# MCU_v3.net
KiCad netlist of a schematic drawn in EAGLE
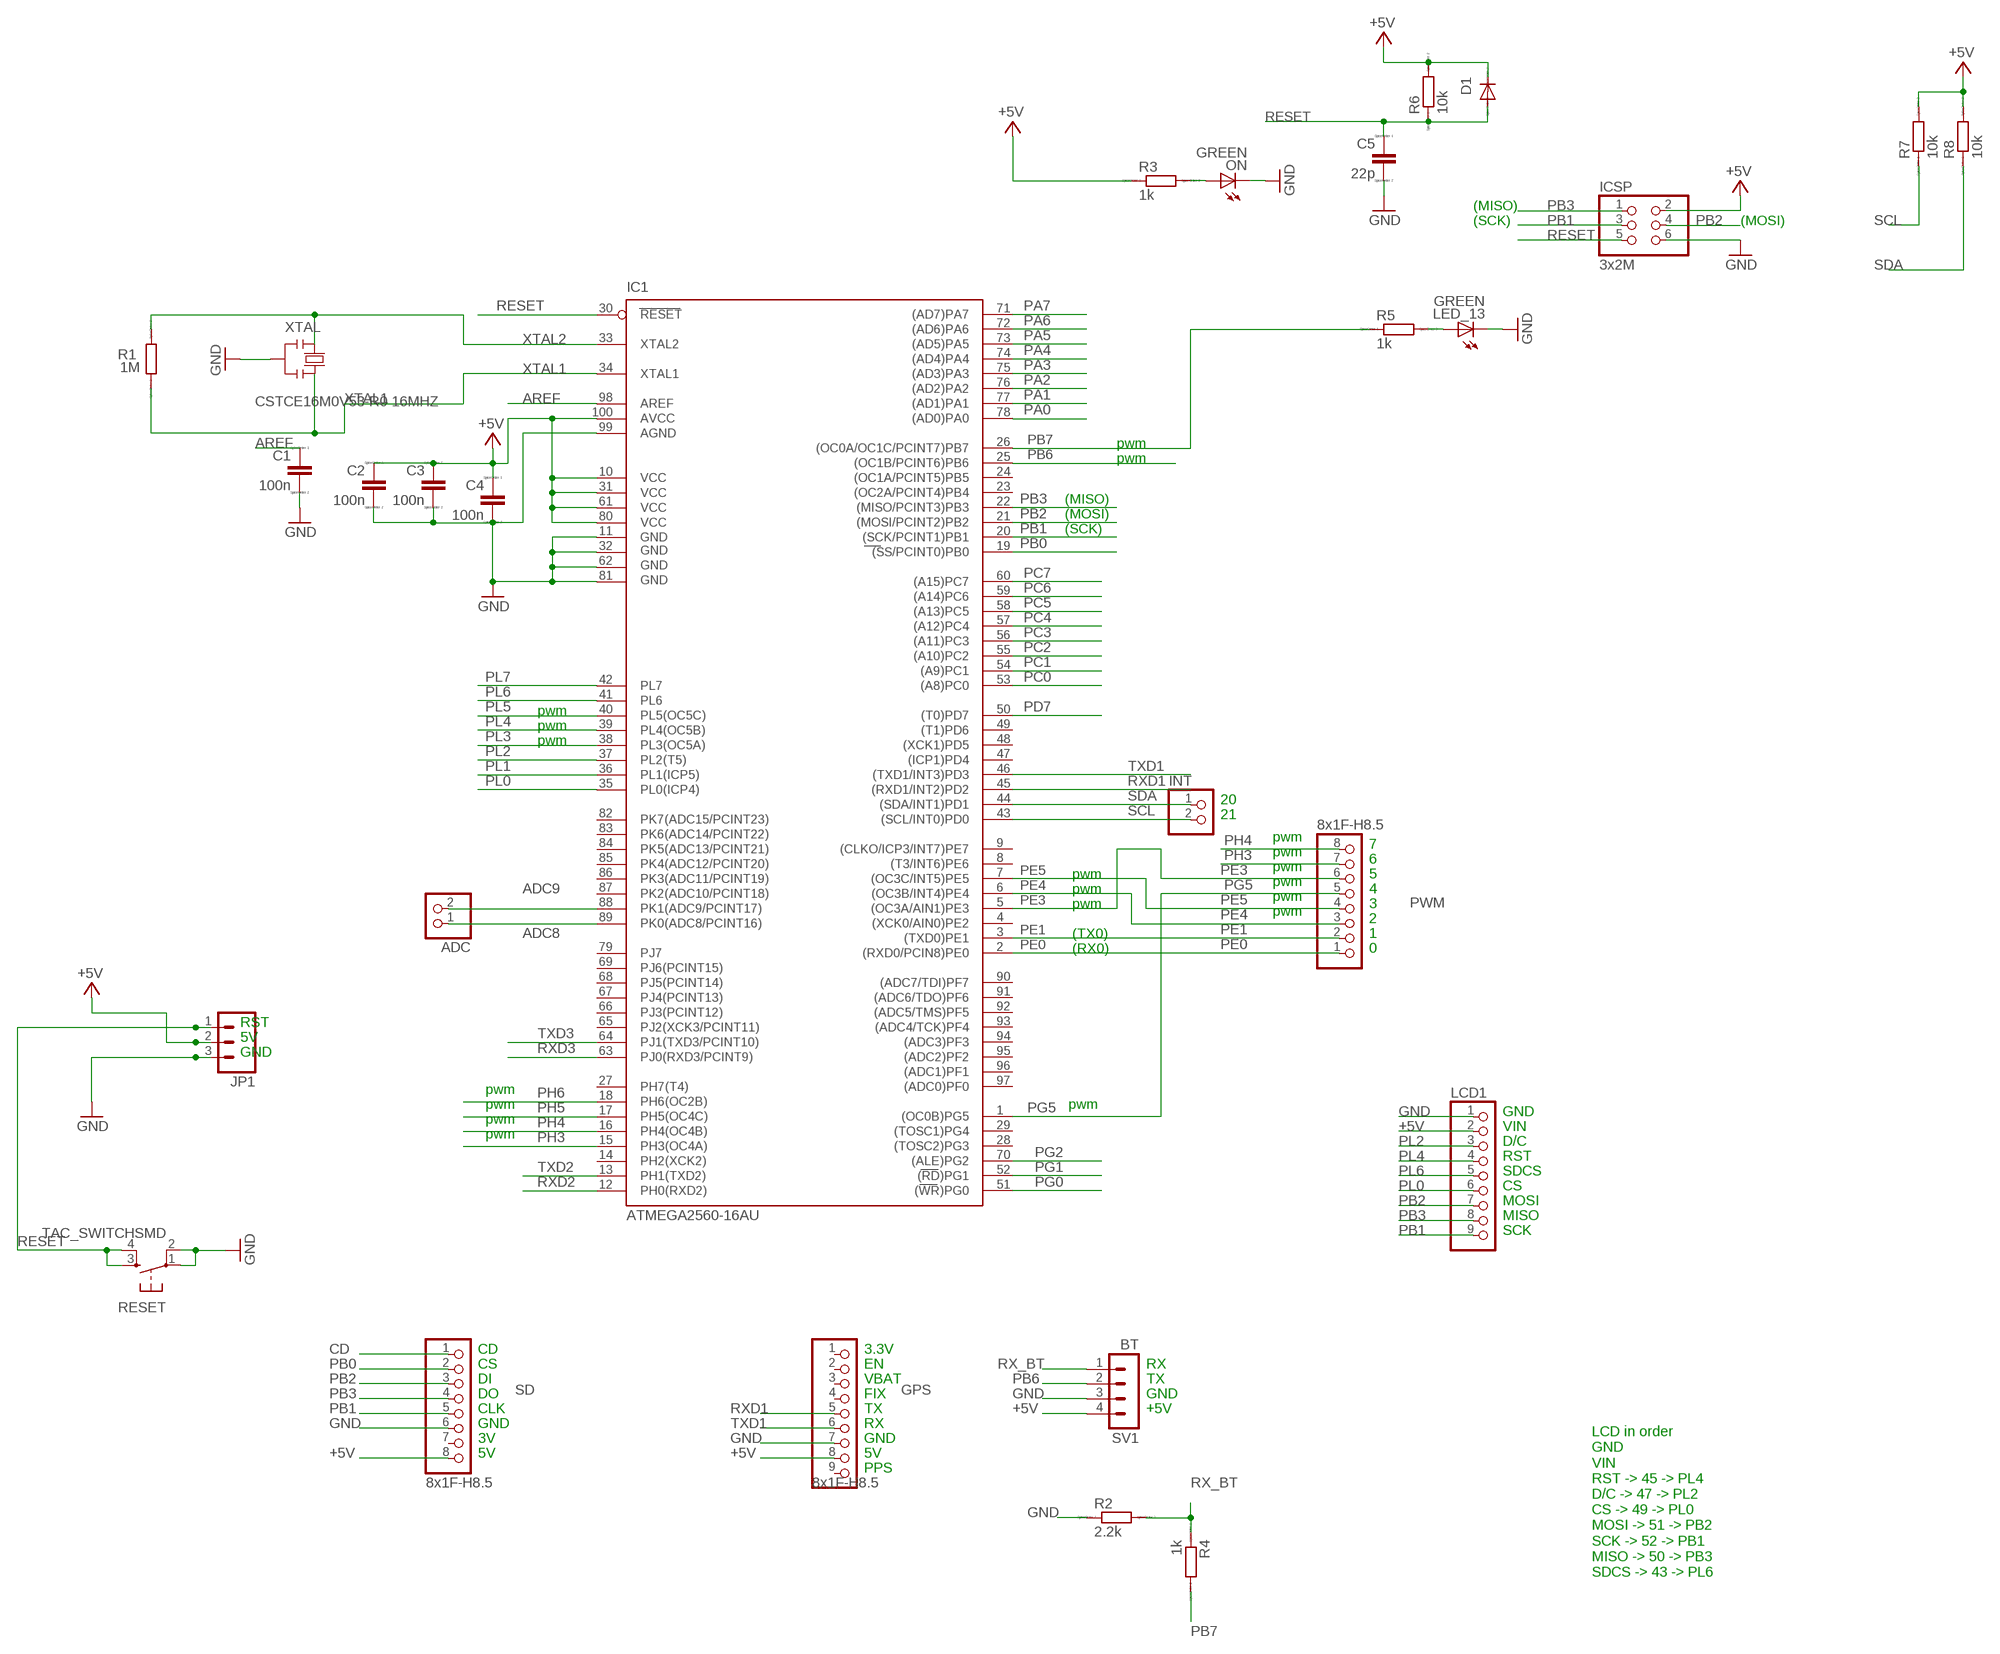
[diagram p0: schematic, sheet 1]

(export (version "E")
  (design (tool "Eeschema 10.0.6"))
  (components
    (comp (ref "ADC")
      (value "PINHD-1X2")
      (footprint "eagle-import:1X02")
      (fields (field (name "MPN") "A21-X0-22-507-115-E"))
      (libsource (lib "eagle-import") (part "PINHD-1X2"))
    )
    (comp (ref "C1")
      (value "100n")
      (footprint "eagle-import:C0805")
      (libsource (lib "eagle-import") (part "C-EUC0805"))
    )
    (comp (ref "C2")
      (value "100n")
      (footprint "eagle-import:C0805")
      (libsource (lib "eagle-import") (part "C-EUC0805"))
    )
    (comp (ref "C3")
      (value "100n")
      (footprint "eagle-import:C0805")
      (libsource (lib "eagle-import") (part "C-EUC0805"))
    )
    (comp (ref "C4")
      (value "100n")
      (footprint "eagle-import:C0805")
      (libsource (lib "eagle-import") (part "C-EUC0805"))
    )
    (comp (ref "C5")
      (value "22p")
      (footprint "eagle-import:C0805")
      (libsource (lib "eagle-import") (part "C-EUC0805"))
    )
    (comp (ref "D1")
      (value "DIODE-MINIMELF")
      (footprint "eagle-import:MINIMELF")
      (libsource (lib "eagle-import") (part "DIODE-MINIMELF"))
    )
    (comp (ref "GPS")
      (value "8x1F-H8.5")
      (footprint "eagle-import:1X09")
      (libsource (lib "eagle-import") (part "PINHD-1X9"))
    )
    (comp (ref "IC1")
      (value "ATMEGA2560-16AU")
      (footprint "eagle-import:TQFP100")
      (libsource (lib "eagle-import") (part "ATMEGA2560AU2560-16"))
    )
    (comp (ref "ICSP")
      (value "3x2M")
      (footprint "eagle-import:2X03")
      (libsource (lib "eagle-import") (part "PINHD-2X3"))
    )
    (comp (ref "INT")
      (value "PINHD-1X2")
      (footprint "eagle-import:1X02")
      (fields (field (name "MPN") "A21-X0-22-507-115-E"))
      (libsource (lib "eagle-import") (part "PINHD-1X2"))
    )
    (comp (ref "JP1")
      (value "M03PTH")
      (footprint "eagle-import:1X03")
      (fields (field (name "MPN") "BI2-Q10S-AZ31X-0.3M-SB3T"))
      (libsource (lib "eagle-import") (part "M03PTH"))
    )
    (comp (ref "LCD1")
      (value "PINHD-1X9")
      (footprint "eagle-import:1X09")
      (libsource (lib "eagle-import") (part "PINHD-1X9"))
    )
    (comp (ref "LED_13")
      (value "GREEN")
      (footprint "eagle-import:CHIP-LED0805")
      (libsource (lib "eagle-import") (part "LEDCHIP-LED0805"))
    )
    (comp (ref "ON")
      (value "GREEN")
      (footprint "eagle-import:CHIP-LED0805")
      (libsource (lib "eagle-import") (part "LEDCHIP-LED0805"))
    )
    (comp (ref "PWM")
      (value "8x1F-H8.5")
      (footprint "eagle-import:1X08")
      (libsource (lib "eagle-import") (part "PINHD-1X8"))
    )
    (comp (ref "R1")
      (value "1M")
      (footprint "eagle-import:R0805")
      (libsource (lib "eagle-import") (part "R-EU_R0805"))
    )
    (comp (ref "R2")
      (value "2.2k")
      (footprint "eagle-import:R0805")
      (libsource (lib "eagle-import") (part "R-EU_R0805"))
    )
    (comp (ref "R3")
      (value "1k")
      (footprint "eagle-import:R0805")
      (libsource (lib "eagle-import") (part "R-EU_R0805"))
    )
    (comp (ref "R4")
      (value "1k")
      (footprint "eagle-import:R0805")
      (libsource (lib "eagle-import") (part "R-EU_R0805"))
    )
    (comp (ref "R5")
      (value "1k")
      (footprint "eagle-import:R0805")
      (libsource (lib "eagle-import") (part "R-EU_R0805"))
    )
    (comp (ref "R6")
      (value "10k")
      (footprint "eagle-import:R0805")
      (libsource (lib "eagle-import") (part "R-EU_R0805"))
    )
    (comp (ref "R7")
      (value "10k")
      (footprint "eagle-import:R0805")
      (libsource (lib "eagle-import") (part "R-EU_R0805"))
    )
    (comp (ref "R8")
      (value "10k")
      (footprint "eagle-import:R0805")
      (libsource (lib "eagle-import") (part "R-EU_R0805"))
    )
    (comp (ref "RESET")
      (value "TAC_SWITCHSMD")
      (footprint "eagle-import:TACTILE-SWITCH-SMD")
      (libsource (lib "eagle-import") (part "TAC_SWITCHSMD"))
    )
    (comp (ref "SD")
      (value "8x1F-H8.5")
      (footprint "eagle-import:1X08")
      (libsource (lib "eagle-import") (part "PINHD-1X8"))
    )
    (comp (ref "SV1")
      (value "BT")
      (footprint "eagle-import:MA04-1")
      (libsource (lib "eagle-import") (part "MA04-1"))
    )
    (comp (ref "XTAL")
      (value "CSTCE16M0V53-R0 16MHZ")
      (footprint "eagle-import:RESONATOR")
      (libsource (lib "eagle-import") (part "RESONATORMU"))
    )
  )
  (nets
    (net (code "1") (name "+5V") (class "Default")
      (node (ref "C2") (pin "1") (pinfunction "1_1") (pintype "passive"))
      (node (ref "C3") (pin "1") (pinfunction "1_1") (pintype "passive"))
      (node (ref "C4") (pin "1") (pinfunction "1_1") (pintype "passive"))
      (node (ref "D1") (pin "C") (pinfunction "C_C") (pintype "passive"))
      (node (ref "GPS") (pin "8") (pinfunction "8_8") (pintype "passive"))
      (node (ref "IC1") (pin "10") (pinfunction "VCC_10") (pintype "power_in"))
      (node (ref "IC1") (pin "100") (pinfunction "AVCC_100") (pintype "power_in"))
      (node (ref "IC1") (pin "31") (pinfunction "VCC1_31") (pintype "power_in"))
      (node (ref "IC1") (pin "61") (pinfunction "VCC2_61") (pintype "power_in"))
      (node (ref "IC1") (pin "80") (pinfunction "VCC3_80") (pintype "power_in"))
      (node (ref "ICSP") (pin "2") (pinfunction "2_2") (pintype "passive"))
      (node (ref "JP1") (pin "2") (pinfunction "2_2") (pintype "passive"))
      (node (ref "LCD1") (pin "2") (pinfunction "2_2") (pintype "passive"))
      (node (ref "R3") (pin "1") (pinfunction "1_1") (pintype "passive"))
      (node (ref "R6") (pin "2") (pinfunction "2_2") (pintype "passive"))
      (node (ref "R7") (pin "2") (pinfunction "2_2") (pintype "passive"))
      (node (ref "R8") (pin "2") (pinfunction "2_2") (pintype "passive"))
      (node (ref "SD") (pin "8") (pinfunction "8_8") (pintype "passive"))
      (node (ref "SV1") (pin "4") (pinfunction "4_4") (pintype "passive"))
    )
    (net (code "2") (name "/ADC8") (class "Default")
      (node (ref "ADC") (pin "1") (pinfunction "1_1") (pintype "passive"))
      (node (ref "IC1") (pin "89") (pinfunction "PK0(ADC8/PCINT16)_89") (pintype "bidirectional"))
    )
    (net (code "3") (name "/ADC9") (class "Default")
      (node (ref "ADC") (pin "2") (pinfunction "2_2") (pintype "passive"))
      (node (ref "IC1") (pin "88") (pinfunction "PK1(ADC9/PCINT17)_88") (pintype "bidirectional"))
    )
    (net (code "4") (name "/AREF") (class "Default")
      (node (ref "C1") (pin "1") (pinfunction "1_1") (pintype "passive"))
      (node (ref "IC1") (pin "98") (pinfunction "AREF_98") (pintype "bidirectional"))
    )
    (net (code "5") (name "/CD") (class "Default")
      (node (ref "SD") (pin "1") (pinfunction "1_1") (pintype "passive"))
    )
    (net (code "6") (name "/PA0") (class "Default")
      (node (ref "IC1") (pin "78") (pinfunction "(AD0)PA0_78") (pintype "bidirectional"))
    )
    (net (code "7") (name "/PA1") (class "Default")
      (node (ref "IC1") (pin "77") (pinfunction "(AD1)PA1_77") (pintype "bidirectional"))
    )
    (net (code "8") (name "/PA2") (class "Default")
      (node (ref "IC1") (pin "76") (pinfunction "(AD2)PA2_76") (pintype "bidirectional"))
    )
    (net (code "9") (name "/PA3") (class "Default")
      (node (ref "IC1") (pin "75") (pinfunction "(AD3)PA3_75") (pintype "bidirectional"))
    )
    (net (code "10") (name "/PA4") (class "Default")
      (node (ref "IC1") (pin "74") (pinfunction "(AD4)PA4_74") (pintype "bidirectional"))
    )
    (net (code "11") (name "/PA5") (class "Default")
      (node (ref "IC1") (pin "73") (pinfunction "(AD5)PA5_73") (pintype "bidirectional"))
    )
    (net (code "12") (name "/PA6") (class "Default")
      (node (ref "IC1") (pin "72") (pinfunction "(AD6)PA6_72") (pintype "bidirectional"))
    )
    (net (code "13") (name "/PA7") (class "Default")
      (node (ref "IC1") (pin "71") (pinfunction "(AD7)PA7_71") (pintype "bidirectional"))
    )
    (net (code "14") (name "/PB0") (class "Default")
      (node (ref "IC1") (pin "19") (pinfunction "(SS/PCINT0)PB0_19") (pintype "bidirectional"))
      (node (ref "SD") (pin "2") (pinfunction "2_2") (pintype "passive"))
    )
    (net (code "15") (name "/PB1") (class "Default")
      (node (ref "IC1") (pin "20") (pinfunction "(SCK/PCINT1)PB1_20") (pintype "bidirectional"))
      (node (ref "ICSP") (pin "3") (pinfunction "3_3") (pintype "passive"))
      (node (ref "LCD1") (pin "9") (pinfunction "9_9") (pintype "passive"))
      (node (ref "SD") (pin "5") (pinfunction "5_5") (pintype "passive"))
    )
    (net (code "16") (name "/PB2") (class "Default")
      (node (ref "IC1") (pin "21") (pinfunction "(MOSI/PCINT2)PB2_21") (pintype "bidirectional"))
      (node (ref "ICSP") (pin "4") (pinfunction "4_4") (pintype "passive"))
      (node (ref "LCD1") (pin "7") (pinfunction "7_7") (pintype "passive"))
      (node (ref "SD") (pin "3") (pinfunction "3_3") (pintype "passive"))
    )
    (net (code "17") (name "/PB3") (class "Default")
      (node (ref "IC1") (pin "22") (pinfunction "(MISO/PCINT3)PB3_22") (pintype "bidirectional"))
      (node (ref "ICSP") (pin "1") (pinfunction "1_1") (pintype "passive"))
      (node (ref "LCD1") (pin "8") (pinfunction "8_8") (pintype "passive"))
      (node (ref "SD") (pin "4") (pinfunction "4_4") (pintype "passive"))
    )
    (net (code "18") (name "/PB6") (class "Default")
      (node (ref "IC1") (pin "25") (pinfunction "(OC1B/PCINT6)PB6_25") (pintype "bidirectional"))
      (node (ref "SV1") (pin "2") (pinfunction "2_2") (pintype "passive"))
    )
    (net (code "19") (name "/PB7") (class "Default")
      (node (ref "IC1") (pin "26") (pinfunction "(OC0A/OC1C/PCINT7)PB7_26") (pintype "bidirectional"))
      (node (ref "R4") (pin "2") (pinfunction "2_2") (pintype "passive"))
      (node (ref "R5") (pin "1") (pinfunction "1_1") (pintype "passive"))
    )
    (net (code "20") (name "/PC0") (class "Default")
      (node (ref "IC1") (pin "53") (pinfunction "(A8)PC0_53") (pintype "bidirectional"))
    )
    (net (code "21") (name "/PC1") (class "Default")
      (node (ref "IC1") (pin "54") (pinfunction "(A9)PC1_54") (pintype "bidirectional"))
    )
    (net (code "22") (name "/PC2") (class "Default")
      (node (ref "IC1") (pin "55") (pinfunction "(A10)PC2_55") (pintype "bidirectional"))
    )
    (net (code "23") (name "/PC3") (class "Default")
      (node (ref "IC1") (pin "56") (pinfunction "(A11)PC3_56") (pintype "bidirectional"))
    )
    (net (code "24") (name "/PC4") (class "Default")
      (node (ref "IC1") (pin "57") (pinfunction "(A12)PC4_57") (pintype "bidirectional"))
    )
    (net (code "25") (name "/PC5") (class "Default")
      (node (ref "IC1") (pin "58") (pinfunction "(A13)PC5_58") (pintype "bidirectional"))
    )
    (net (code "26") (name "/PC6") (class "Default")
      (node (ref "IC1") (pin "59") (pinfunction "(A14)PC6_59") (pintype "bidirectional"))
    )
    (net (code "27") (name "/PC7") (class "Default")
      (node (ref "IC1") (pin "60") (pinfunction "(A15)PC7_60") (pintype "bidirectional"))
    )
    (net (code "28") (name "/PD7") (class "Default")
      (node (ref "IC1") (pin "50") (pinfunction "(T0)PD7_50") (pintype "bidirectional"))
    )
    (net (code "29") (name "/PE0") (class "Default")
      (node (ref "IC1") (pin "2") (pinfunction "(RXD0/PCIN8)PE0_2") (pintype "bidirectional"))
      (node (ref "PWM") (pin "1") (pinfunction "1_1") (pintype "passive"))
    )
    (net (code "30") (name "/PE1") (class "Default")
      (node (ref "IC1") (pin "3") (pinfunction "(TXD0)PE1_3") (pintype "bidirectional"))
      (node (ref "PWM") (pin "2") (pinfunction "2_2") (pintype "passive"))
    )
    (net (code "31") (name "/PE3") (class "Default")
      (node (ref "IC1") (pin "5") (pinfunction "(OC3A/AIN1)PE3_5") (pintype "bidirectional"))
      (node (ref "PWM") (pin "6") (pinfunction "6_6") (pintype "passive"))
    )
    (net (code "32") (name "/PE4") (class "Default")
      (node (ref "IC1") (pin "6") (pinfunction "(OC3B/INT4)PE4_6") (pintype "bidirectional"))
      (node (ref "PWM") (pin "3") (pinfunction "3_3") (pintype "passive"))
    )
    (net (code "33") (name "/PE5") (class "Default")
      (node (ref "IC1") (pin "7") (pinfunction "(OC3C/INT5)PE5_7") (pintype "bidirectional"))
      (node (ref "PWM") (pin "4") (pinfunction "4_4") (pintype "passive"))
    )
    (net (code "34") (name "/PG0") (class "Default")
      (node (ref "IC1") (pin "51") (pinfunction "(WR)PG0_51") (pintype "bidirectional"))
    )
    (net (code "35") (name "/PG1") (class "Default")
      (node (ref "IC1") (pin "52") (pinfunction "(RD)PG1_52") (pintype "bidirectional"))
    )
    (net (code "36") (name "/PG2") (class "Default")
      (node (ref "IC1") (pin "70") (pinfunction "(ALE)PG2_70") (pintype "bidirectional"))
    )
    (net (code "37") (name "/PG5") (class "Default")
      (node (ref "IC1") (pin "1") (pinfunction "(OC0B)PG5_1") (pintype "bidirectional"))
      (node (ref "PWM") (pin "5") (pinfunction "5_5") (pintype "passive"))
    )
    (net (code "38") (name "/PH3") (class "Default")
      (node (ref "IC1") (pin "15") (pinfunction "PH3(OC4A)_15") (pintype "bidirectional"))
      (node (ref "PWM") (pin "7") (pinfunction "7_7") (pintype "passive"))
    )
    (net (code "39") (name "/PH4") (class "Default")
      (node (ref "IC1") (pin "16") (pinfunction "PH4(OC4B)_16") (pintype "bidirectional"))
      (node (ref "PWM") (pin "8") (pinfunction "8_8") (pintype "passive"))
    )
    (net (code "40") (name "/PH5") (class "Default")
      (node (ref "IC1") (pin "17") (pinfunction "PH5(OC4C)_17") (pintype "bidirectional"))
    )
    (net (code "41") (name "/PH6") (class "Default")
      (node (ref "IC1") (pin "18") (pinfunction "PH6(OC2B)_18") (pintype "bidirectional"))
    )
    (net (code "42") (name "/PL0") (class "Default")
      (node (ref "IC1") (pin "35") (pinfunction "PL0(ICP4)_35") (pintype "bidirectional"))
      (node (ref "LCD1") (pin "6") (pinfunction "6_6") (pintype "passive"))
    )
    (net (code "43") (name "/PL1") (class "Default")
      (node (ref "IC1") (pin "36") (pinfunction "PL1(ICP5)_36") (pintype "bidirectional"))
    )
    (net (code "44") (name "/PL2") (class "Default")
      (node (ref "IC1") (pin "37") (pinfunction "PL2(T5)_37") (pintype "bidirectional"))
      (node (ref "LCD1") (pin "3") (pinfunction "3_3") (pintype "passive"))
    )
    (net (code "45") (name "/PL3") (class "Default")
      (node (ref "IC1") (pin "38") (pinfunction "PL3(OC5A)_38") (pintype "bidirectional"))
    )
    (net (code "46") (name "/PL4") (class "Default")
      (node (ref "IC1") (pin "39") (pinfunction "PL4(OC5B)_39") (pintype "bidirectional"))
      (node (ref "LCD1") (pin "4") (pinfunction "4_4") (pintype "passive"))
    )
    (net (code "47") (name "/PL5") (class "Default")
      (node (ref "IC1") (pin "40") (pinfunction "PL5(OC5C)_40") (pintype "bidirectional"))
    )
    (net (code "48") (name "/PL6") (class "Default")
      (node (ref "IC1") (pin "41") (pinfunction "PL6_41") (pintype "bidirectional"))
      (node (ref "LCD1") (pin "5") (pinfunction "5_5") (pintype "passive"))
    )
    (net (code "49") (name "/PL7") (class "Default")
      (node (ref "IC1") (pin "42") (pinfunction "PL7_42") (pintype "bidirectional"))
    )
    (net (code "50") (name "/RESET") (class "Default")
      (node (ref "C5") (pin "1") (pinfunction "1_1") (pintype "passive"))
      (node (ref "D1") (pin "A") (pinfunction "A_A") (pintype "passive"))
      (node (ref "IC1") (pin "30") (pinfunction "RESET_30") (pintype "input"))
      (node (ref "ICSP") (pin "5") (pinfunction "5_5") (pintype "passive"))
      (node (ref "JP1") (pin "1") (pinfunction "1_1") (pintype "passive"))
      (node (ref "R6") (pin "1") (pinfunction "1_1") (pintype "passive"))
      (node (ref "RESET") (pin "3") (pinfunction "3_3") (pintype "passive"))
      (node (ref "RESET") (pin "4") (pinfunction "4_4") (pintype "passive"))
    )
    (net (code "51") (name "/RXD1") (class "Default")
      (node (ref "GPS") (pin "5") (pinfunction "5_5") (pintype "passive"))
      (node (ref "IC1") (pin "45") (pinfunction "(RXD1/INT2)PD2_45") (pintype "bidirectional"))
    )
    (net (code "52") (name "/RXD2") (class "Default")
      (node (ref "IC1") (pin "12") (pinfunction "PH0(RXD2)_12") (pintype "bidirectional"))
    )
    (net (code "53") (name "/RXD3") (class "Default")
      (node (ref "IC1") (pin "63") (pinfunction "PJ0(RXD3/PCINT9)_63") (pintype "bidirectional"))
    )
    (net (code "54") (name "/RX_BT") (class "Default")
      (node (ref "R2") (pin "2") (pinfunction "2_2") (pintype "passive"))
      (node (ref "R4") (pin "1") (pinfunction "1_1") (pintype "passive"))
      (node (ref "SV1") (pin "1") (pinfunction "1_1") (pintype "passive"))
    )
    (net (code "55") (name "/SCL") (class "Default")
      (node (ref "IC1") (pin "43") (pinfunction "(SCL/INT0)PD0_43") (pintype "bidirectional"))
      (node (ref "INT") (pin "2") (pinfunction "2_2") (pintype "passive"))
      (node (ref "R7") (pin "1") (pinfunction "1_1") (pintype "passive"))
    )
    (net (code "56") (name "/SDA") (class "Default")
      (node (ref "IC1") (pin "44") (pinfunction "(SDA/INT1)PD1_44") (pintype "bidirectional"))
      (node (ref "INT") (pin "1") (pinfunction "1_1") (pintype "passive"))
      (node (ref "R8") (pin "1") (pinfunction "1_1") (pintype "passive"))
    )
    (net (code "57") (name "/TXD1") (class "Default")
      (node (ref "GPS") (pin "6") (pinfunction "6_6") (pintype "passive"))
      (node (ref "IC1") (pin "46") (pinfunction "(TXD1/INT3)PD3_46") (pintype "bidirectional"))
    )
    (net (code "58") (name "/TXD2") (class "Default")
      (node (ref "IC1") (pin "13") (pinfunction "PH1(TXD2)_13") (pintype "bidirectional"))
    )
    (net (code "59") (name "/TXD3") (class "Default")
      (node (ref "IC1") (pin "64") (pinfunction "PJ1(TXD3/PCINT10)_64") (pintype "bidirectional"))
    )
    (net (code "60") (name "/XTAL1") (class "Default")
      (node (ref "IC1") (pin "34") (pinfunction "XTAL1_34") (pintype "input"))
      (node (ref "R1") (pin "1") (pinfunction "1_1") (pintype "passive"))
      (node (ref "XTAL") (pin "3") (pinfunction "3_3") (pintype "passive"))
    )
    (net (code "61") (name "/XTAL2") (class "Default")
      (node (ref "IC1") (pin "33") (pinfunction "XTAL2_33") (pintype "output"))
      (node (ref "R1") (pin "2") (pinfunction "2_2") (pintype "passive"))
      (node (ref "XTAL") (pin "1") (pinfunction "1_1") (pintype "passive"))
    )
    (net (code "62") (name "GND") (class "Default")
      (node (ref "C1") (pin "2") (pinfunction "2_2") (pintype "passive"))
      (node (ref "C2") (pin "2") (pinfunction "2_2") (pintype "passive"))
      (node (ref "C3") (pin "2") (pinfunction "2_2") (pintype "passive"))
      (node (ref "C4") (pin "2") (pinfunction "2_2") (pintype "passive"))
      (node (ref "C5") (pin "2") (pinfunction "2_2") (pintype "passive"))
      (node (ref "GPS") (pin "7") (pinfunction "7_7") (pintype "passive"))
      (node (ref "IC1") (pin "11") (pinfunction "GND_11") (pintype "power_in"))
      (node (ref "IC1") (pin "32") (pinfunction "GND1_32") (pintype "power_in"))
      (node (ref "IC1") (pin "62") (pinfunction "GND2_62") (pintype "power_in"))
      (node (ref "IC1") (pin "81") (pinfunction "GND3_81") (pintype "power_in"))
      (node (ref "IC1") (pin "99") (pinfunction "AGND_99") (pintype "power_in"))
      (node (ref "ICSP") (pin "6") (pinfunction "6_6") (pintype "passive"))
      (node (ref "JP1") (pin "3") (pinfunction "3_3") (pintype "passive"))
      (node (ref "LCD1") (pin "1") (pinfunction "1_1") (pintype "passive"))
      (node (ref "LED_13") (pin "C") (pinfunction "C_C") (pintype "passive"))
      (node (ref "ON") (pin "C") (pinfunction "C_C") (pintype "passive"))
      (node (ref "R2") (pin "1") (pinfunction "1_1") (pintype "passive"))
      (node (ref "RESET") (pin "1") (pinfunction "1_1") (pintype "passive"))
      (node (ref "RESET") (pin "2") (pinfunction "2_2") (pintype "passive"))
      (node (ref "SD") (pin "6") (pinfunction "6_6") (pintype "passive"))
      (node (ref "SV1") (pin "3") (pinfunction "3_3") (pintype "passive"))
      (node (ref "XTAL") (pin "2") (pinfunction "2_2") (pintype "passive"))
    )
    (net (code "63") (name "Net-(LED_13-PadA)") (class "Default")
      (node (ref "LED_13") (pin "A") (pinfunction "A_A") (pintype "passive"))
      (node (ref "R5") (pin "2") (pinfunction "2_2") (pintype "passive"))
    )
    (net (code "64") (name "Net-(ON-PadA)") (class "Default")
      (node (ref "ON") (pin "A") (pinfunction "A_A") (pintype "passive"))
      (node (ref "R3") (pin "2") (pinfunction "2_2") (pintype "passive"))
    )
    (net (code "65") (name "unconnected-(GPS-Pad1)") (class "Default")
      (node (ref "GPS") (pin "1") (pinfunction "1_1") (pintype "passive"))
    )
    (net (code "66") (name "unconnected-(GPS-Pad2)") (class "Default")
      (node (ref "GPS") (pin "2") (pinfunction "2_2") (pintype "passive"))
    )
    (net (code "67") (name "unconnected-(GPS-Pad3)") (class "Default")
      (node (ref "GPS") (pin "3") (pinfunction "3_3") (pintype "passive"))
    )
    (net (code "68") (name "unconnected-(GPS-Pad4)") (class "Default")
      (node (ref "GPS") (pin "4") (pinfunction "4_4") (pintype "passive"))
    )
    (net (code "69") (name "unconnected-(GPS-Pad9)") (class "Default")
      (node (ref "GPS") (pin "9") (pinfunction "9_9") (pintype "passive"))
    )
    (net (code "70") (name "unconnected-(IC1-(ADC0)PF0-Pad97)") (class "Default")
      (node (ref "IC1") (pin "97") (pinfunction "(ADC0)PF0_97") (pintype "bidirectional"))
    )
    (net (code "71") (name "unconnected-(IC1-(ADC1)PF1-Pad96)") (class "Default")
      (node (ref "IC1") (pin "96") (pinfunction "(ADC1)PF1_96") (pintype "bidirectional"))
    )
    (net (code "72") (name "unconnected-(IC1-(ADC2)PF2-Pad95)") (class "Default")
      (node (ref "IC1") (pin "95") (pinfunction "(ADC2)PF2_95") (pintype "bidirectional"))
    )
    (net (code "73") (name "unconnected-(IC1-(ADC3)PF3-Pad94)") (class "Default")
      (node (ref "IC1") (pin "94") (pinfunction "(ADC3)PF3_94") (pintype "bidirectional"))
    )
    (net (code "74") (name "unconnected-(IC1-(ADC4{slash}TCK)PF4-Pad93)") (class "Default")
      (node (ref "IC1") (pin "93") (pinfunction "(ADC4/TCK)PF4_93") (pintype "bidirectional"))
    )
    (net (code "75") (name "unconnected-(IC1-(ADC5{slash}TMS)PF5-Pad92)") (class "Default")
      (node (ref "IC1") (pin "92") (pinfunction "(ADC5/TMS)PF5_92") (pintype "bidirectional"))
    )
    (net (code "76") (name "unconnected-(IC1-(ADC6{slash}TDO)PF6-Pad91)") (class "Default")
      (node (ref "IC1") (pin "91") (pinfunction "(ADC6/TDO)PF6_91") (pintype "bidirectional"))
    )
    (net (code "77") (name "unconnected-(IC1-(ADC7{slash}TDI)PF7-Pad90)") (class "Default")
      (node (ref "IC1") (pin "90") (pinfunction "(ADC7/TDI)PF7_90") (pintype "bidirectional"))
    )
    (net (code "78") (name "unconnected-(IC1-(CLKO{slash}ICP3{slash}INT7)PE7-Pad9)") (class "Default")
      (node (ref "IC1") (pin "9") (pinfunction "(CLKO/ICP3/INT7)PE7_9") (pintype "bidirectional"))
    )
    (net (code "79") (name "unconnected-(IC1-(ICP1)PD4-Pad47)") (class "Default")
      (node (ref "IC1") (pin "47") (pinfunction "(ICP1)PD4_47") (pintype "bidirectional"))
    )
    (net (code "80") (name "unconnected-(IC1-(OC1A{slash}PCINT5)PB5-Pad24)") (class "Default")
      (node (ref "IC1") (pin "24") (pinfunction "(OC1A/PCINT5)PB5_24") (pintype "bidirectional"))
    )
    (net (code "81") (name "unconnected-(IC1-(OC2A{slash}PCINT4)PB4-Pad23)") (class "Default")
      (node (ref "IC1") (pin "23") (pinfunction "(OC2A/PCINT4)PB4_23") (pintype "bidirectional"))
    )
    (net (code "82") (name "unconnected-(IC1-(T1)PD6-Pad49)") (class "Default")
      (node (ref "IC1") (pin "49") (pinfunction "(T1)PD6_49") (pintype "bidirectional"))
    )
    (net (code "83") (name "unconnected-(IC1-(T3{slash}INT6)PE6-Pad8)") (class "Default")
      (node (ref "IC1") (pin "8") (pinfunction "(T3/INT6)PE6_8") (pintype "bidirectional"))
    )
    (net (code "84") (name "unconnected-(IC1-(TOSC1)PG4-Pad29)") (class "Default")
      (node (ref "IC1") (pin "29") (pinfunction "(TOSC1)PG4_29") (pintype "bidirectional"))
    )
    (net (code "85") (name "unconnected-(IC1-(TOSC2)PG3-Pad28)") (class "Default")
      (node (ref "IC1") (pin "28") (pinfunction "(TOSC2)PG3_28") (pintype "bidirectional"))
    )
    (net (code "86") (name "unconnected-(IC1-(XCK0{slash}AIN0)PE2-Pad4)") (class "Default")
      (node (ref "IC1") (pin "4") (pinfunction "(XCK0/AIN0)PE2_4") (pintype "bidirectional"))
    )
    (net (code "87") (name "unconnected-(IC1-(XCK1)PD5-Pad48)") (class "Default")
      (node (ref "IC1") (pin "48") (pinfunction "(XCK1)PD5_48") (pintype "bidirectional"))
    )
    (net (code "88") (name "unconnected-(IC1-PH2(XCK2)-Pad14)") (class "Default")
      (node (ref "IC1") (pin "14") (pinfunction "PH2(XCK2)_14") (pintype "bidirectional"))
    )
    (net (code "89") (name "unconnected-(IC1-PH7(T4)-Pad27)") (class "Default")
      (node (ref "IC1") (pin "27") (pinfunction "PH7(T4)_27") (pintype "bidirectional"))
    )
    (net (code "90") (name "unconnected-(IC1-PJ2(XCK3{slash}PCINT11)-Pad65)") (class "Default")
      (node (ref "IC1") (pin "65") (pinfunction "PJ2(XCK3/PCINT11)_65") (pintype "bidirectional"))
    )
    (net (code "91") (name "unconnected-(IC1-PJ3(PCINT12)-Pad66)") (class "Default")
      (node (ref "IC1") (pin "66") (pinfunction "PJ3(PCINT12)_66") (pintype "bidirectional"))
    )
    (net (code "92") (name "unconnected-(IC1-PJ4(PCINT13)-Pad67)") (class "Default")
      (node (ref "IC1") (pin "67") (pinfunction "PJ4(PCINT13)_67") (pintype "bidirectional"))
    )
    (net (code "93") (name "unconnected-(IC1-PJ5(PCINT14)-Pad68)") (class "Default")
      (node (ref "IC1") (pin "68") (pinfunction "PJ5(PCINT14)_68") (pintype "bidirectional"))
    )
    (net (code "94") (name "unconnected-(IC1-PJ6(PCINT15)-Pad69)") (class "Default")
      (node (ref "IC1") (pin "69") (pinfunction "PJ6(PCINT15)_69") (pintype "bidirectional"))
    )
    (net (code "95") (name "unconnected-(IC1-PJ7-Pad79)") (class "Default")
      (node (ref "IC1") (pin "79") (pinfunction "PJ7_79") (pintype "bidirectional"))
    )
    (net (code "96") (name "unconnected-(IC1-PK2(ADC10{slash}PCINT18)-Pad87)") (class "Default")
      (node (ref "IC1") (pin "87") (pinfunction "PK2(ADC10/PCINT18)_87") (pintype "bidirectional"))
    )
    (net (code "97") (name "unconnected-(IC1-PK3(ADC11{slash}PCINT19)-Pad86)") (class "Default")
      (node (ref "IC1") (pin "86") (pinfunction "PK3(ADC11/PCINT19)_86") (pintype "bidirectional"))
    )
    (net (code "98") (name "unconnected-(IC1-PK4(ADC12{slash}PCINT20)-Pad85)") (class "Default")
      (node (ref "IC1") (pin "85") (pinfunction "PK4(ADC12/PCINT20)_85") (pintype "bidirectional"))
    )
    (net (code "99") (name "unconnected-(IC1-PK5(ADC13{slash}PCINT21)-Pad84)") (class "Default")
      (node (ref "IC1") (pin "84") (pinfunction "PK5(ADC13/PCINT21)_84") (pintype "bidirectional"))
    )
    (net (code "100") (name "unconnected-(IC1-PK6(ADC14{slash}PCINT22)-Pad83)") (class "Default")
      (node (ref "IC1") (pin "83") (pinfunction "PK6(ADC14/PCINT22)_83") (pintype "bidirectional"))
    )
    (net (code "101") (name "unconnected-(IC1-PK7(ADC15{slash}PCINT23)-Pad82)") (class "Default")
      (node (ref "IC1") (pin "82") (pinfunction "PK7(ADC15/PCINT23)_82") (pintype "bidirectional"))
    )
    (net (code "102") (name "unconnected-(SD-Pad7)") (class "Default")
      (node (ref "SD") (pin "7") (pinfunction "7_7") (pintype "passive"))
    )
  )
)
